# Connectors.net
KiCad netlist of a schematic drawn in Altium Designer
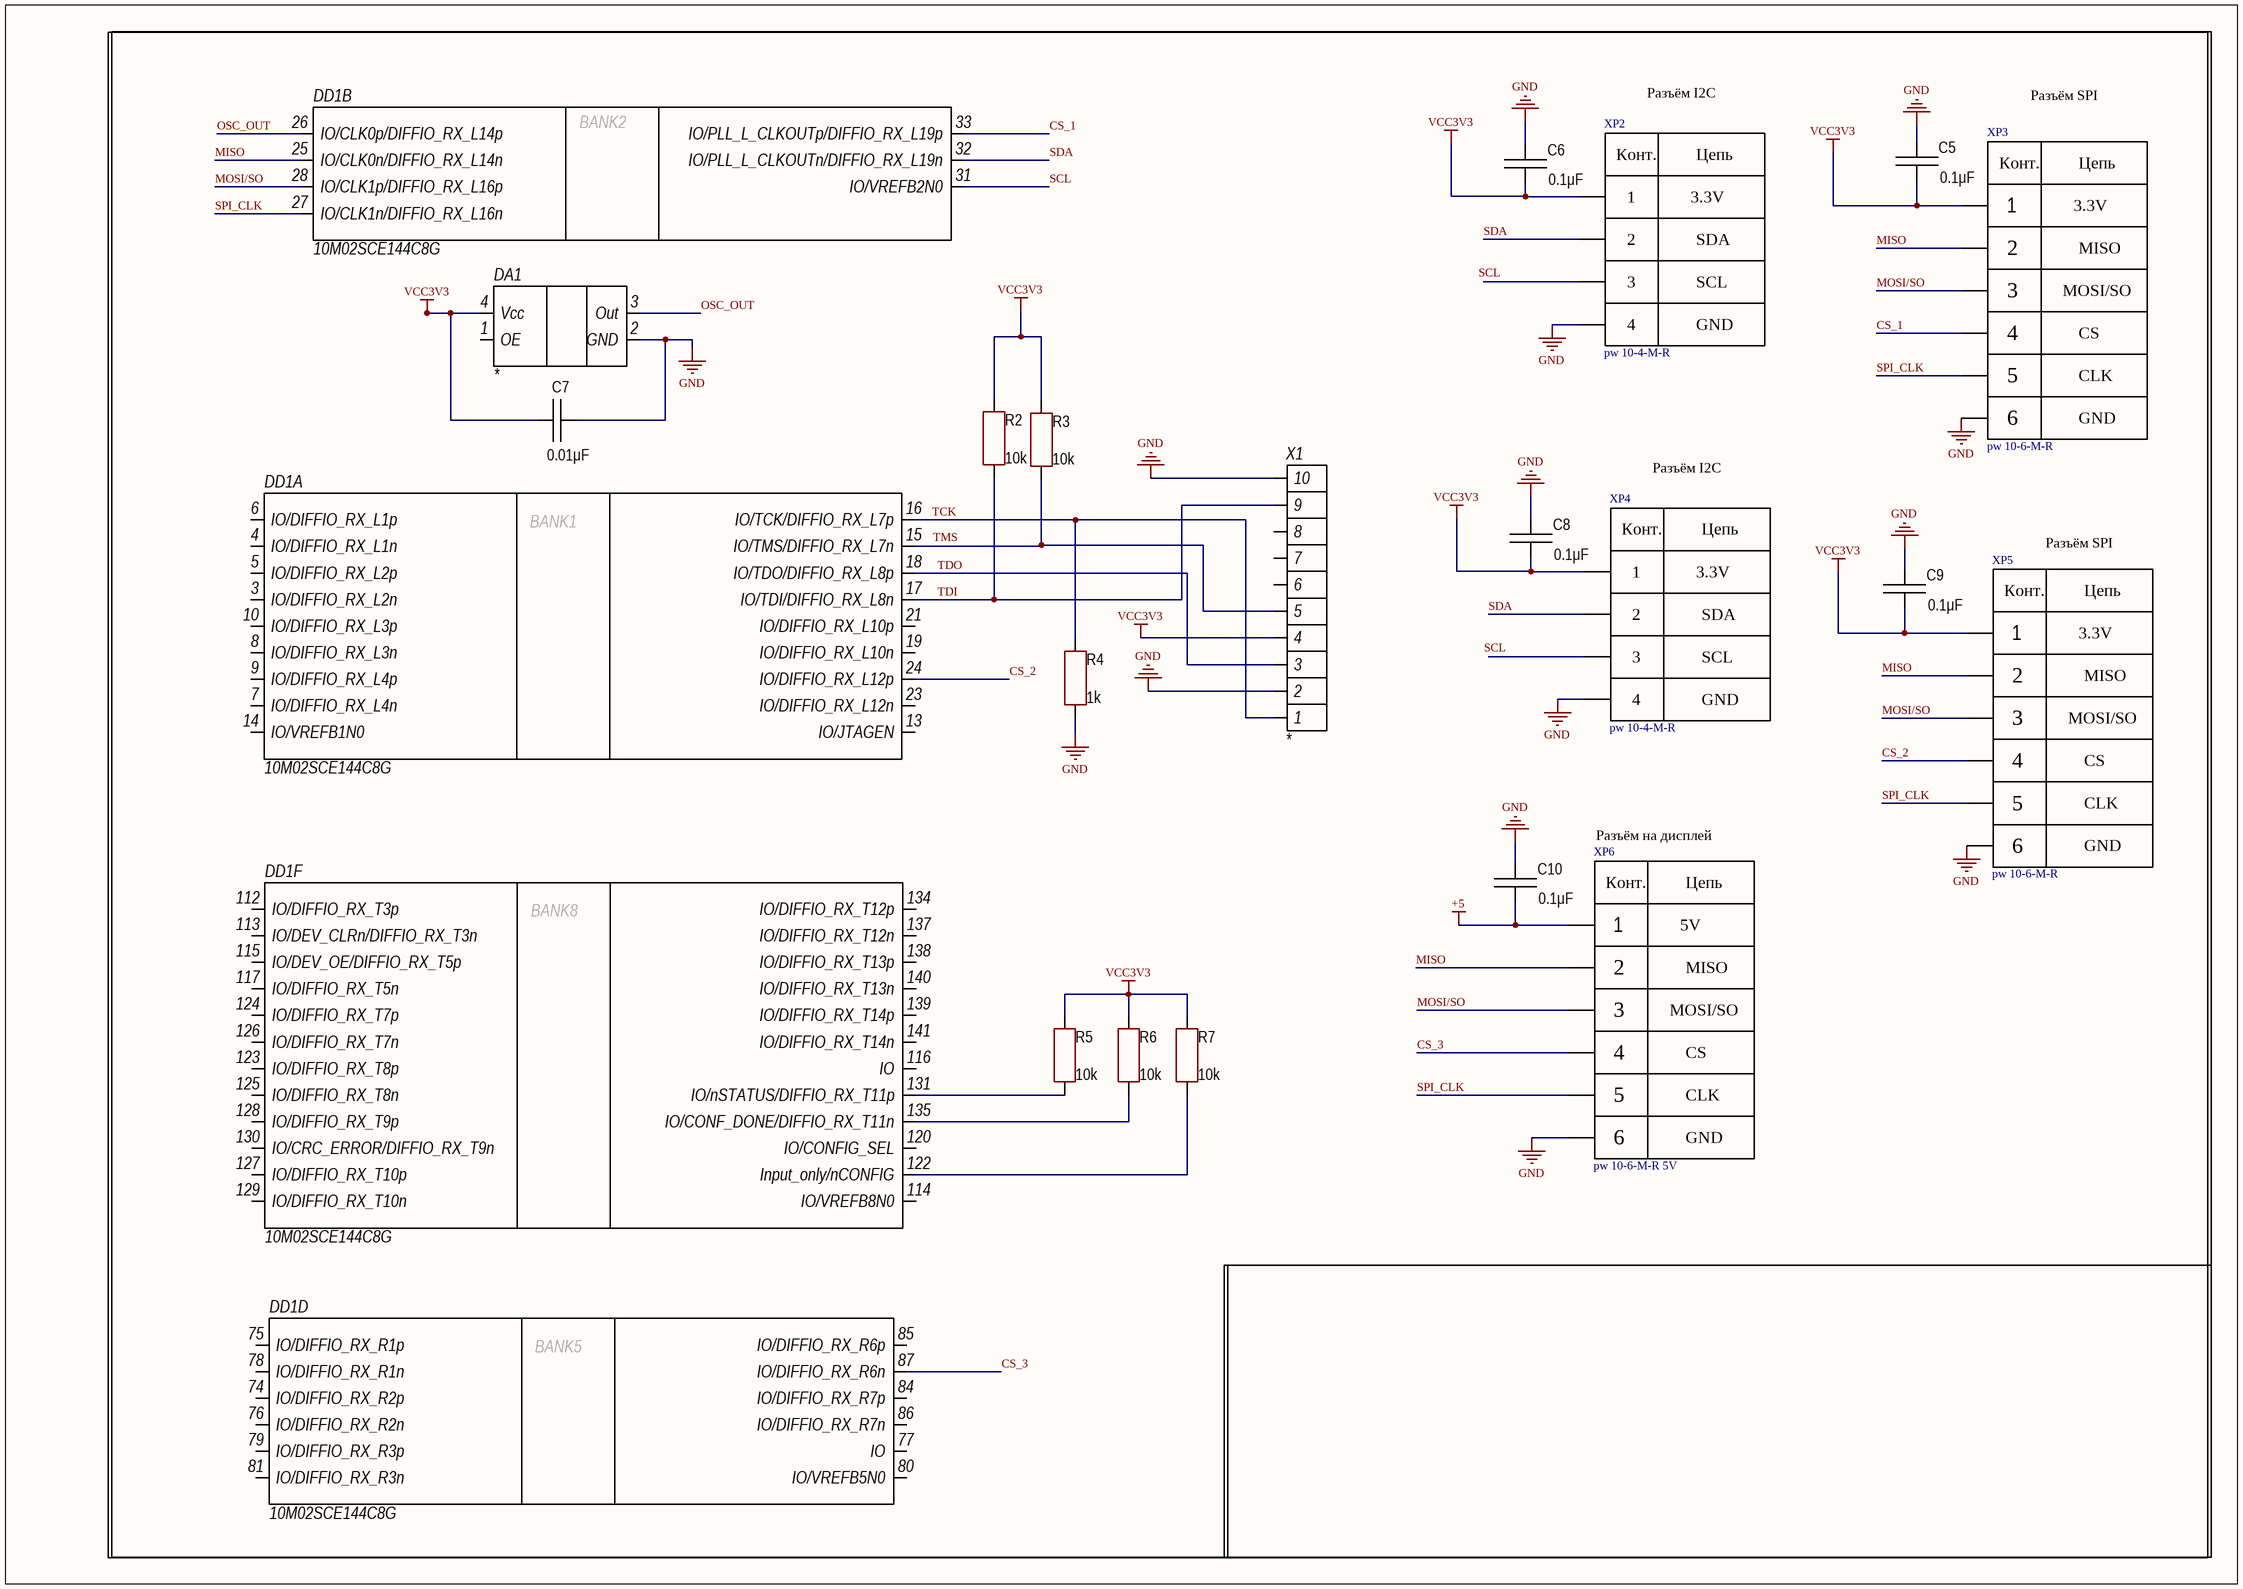
[diagram p0: Connectors.SchDoc]

(export (version "E")
  (design (tool "Eeschema 10.0.6"))
  (components
    (comp (ref "C5")
      (value "0.1μF")
      (footprint "CAP: 0805")
      (fields (field (name "VALUEMANUFACTURERPARTNUMBER") "Ceramic capacitor, 0.1μF, X7R, , , 0805, "))
      (libsource (lib "Capacitor") (part "Ceramic_0805"))
    )
    (comp (ref "C6")
      (value "0.1μF")
      (footprint "CAP: 0805")
      (fields (field (name "VALUEMANUFACTURERPARTNUMBER") "Ceramic capacitor, 0.1μF, X7R, , , 0805, "))
      (libsource (lib "Capacitor") (part "Ceramic_0805"))
    )
    (comp (ref "C7")
      (value "0.01μF")
      (footprint "CAP: 0805")
      (fields (field (name "VALUEMANUFACTURERPARTNUMBER") "Ceramic capacitor, 0.01μF, X7R, , , 0805, "))
      (libsource (lib "Capacitor") (part "Ceramic_0805"))
    )
    (comp (ref "C8")
      (value "0.1μF")
      (footprint "CAP: 0805")
      (fields (field (name "VALUEMANUFACTURERPARTNUMBER") "Ceramic capacitor, 0.1μF, X7R, , , 0805, "))
      (libsource (lib "Capacitor") (part "Ceramic_0805"))
    )
    (comp (ref "C9")
      (value "0.1μF")
      (footprint "CAP: 0805")
      (fields (field (name "VALUEMANUFACTURERPARTNUMBER") "Ceramic capacitor, 0.1μF, X7R, , , 0805, "))
      (libsource (lib "Capacitor") (part "Ceramic_0805"))
    )
    (comp (ref "C10")
      (value "0.1μF")
      (footprint "CAP: 0805")
      (fields (field (name "VALUEMANUFACTURERPARTNUMBER") "Ceramic capacitor, 0.1μF, X7R, , , 0805, "))
      (libsource (lib "Capacitor") (part "Ceramic_0805"))
    )
    (comp (ref "DA1")
      (value "*")
      (footprint "4-SMD, NO LEAD")
      (description "Oscillator")
      (fields (field (name "MANUFACTURER") "EPSON"))
      (libsource (lib "Integrated_Library") (part "SG 8002"))
    )
    (comp (ref "DD1")
      (value "10M02SCE144C8G")
      (footprint "144-Lead EQFP")
      (description "MAX10 FPGA")
      (fields (field (name "MANUFACTURER") "Intel"))
      (libsource (lib "Integrated_Library") (part "10M02SCE144C8G"))
    )
    (comp (ref "R2")
      (value "10k")
      (footprint "RES: 0805")
      (fields (field (name "VALUEMANUFACTURERPARTNUMBER") "Resistor film, 10k, , 0805, , "))
      (libsource (lib "Resistor") (part "Resistor_0805"))
    )
    (comp (ref "R3")
      (value "10k")
      (footprint "RES: 0805")
      (fields (field (name "VALUEMANUFACTURERPARTNUMBER") "Resistor film, 10k, , 0805, , "))
      (libsource (lib "Resistor") (part "Resistor_0805"))
    )
    (comp (ref "R4")
      (value "1k")
      (footprint "RES: 0805")
      (fields (field (name "VALUEMANUFACTURERPARTNUMBER") "Resistor film, 1k, , 0805, , "))
      (libsource (lib "Resistor") (part "Resistor_0805"))
    )
    (comp (ref "R5")
      (value "10k")
      (footprint "RES: 0805")
      (fields (field (name "VALUEMANUFACTURERPARTNUMBER") "Resistor film, 10k, , 0805, , "))
      (libsource (lib "Resistor") (part "Resistor_0805"))
    )
    (comp (ref "R6")
      (value "10k")
      (footprint "RES: 0805")
      (fields (field (name "VALUEMANUFACTURERPARTNUMBER") "Resistor film, 10k, , 0805, , "))
      (libsource (lib "Resistor") (part "Resistor_0805"))
    )
    (comp (ref "R7")
      (value "10k")
      (footprint "RES: 0805")
      (fields (field (name "VALUEMANUFACTURERPARTNUMBER") "Resistor film, 10k, , 0805, , "))
      (libsource (lib "Resistor") (part "Resistor_0805"))
    )
    (comp (ref "X1")
      (value "*")
      (footprint "IDC-10MS")
      (description "Connector")
      (libsource (lib "Integrated_Library") (part "Connector 10-pin"))
    )
    (comp (ref "XP2")
      (value "pw 10-4-M-R")
      (footprint "PW 10-4 - M - R")
      (libsource (lib "Integrated_Library") (part "pw 10-4-M-R"))
    )
    (comp (ref "XP3")
      (value "pw 10-6-M-R")
      (footprint "PW 10-6-M")
      (libsource (lib "Integrated_Library") (part "pw 10-6-M-R"))
    )
    (comp (ref "XP4")
      (value "pw 10-4-M-R")
      (footprint "PW 10-4 - M - R")
      (libsource (lib "Integrated_Library") (part "pw 10-4-M-R"))
    )
    (comp (ref "XP5")
      (value "pw 10-6-M-R")
      (footprint "PW 10-6-M")
      (libsource (lib "Integrated_Library") (part "pw 10-6-M-R"))
    )
    (comp (ref "XP6")
      (value "pw 10-6-M-R 5V")
      (footprint "PW 10-6-M")
      (libsource (lib "Integrated_Library") (part "pw 10-6-M-R 5V"))
    )
  )
  (nets
    (net (code "1") (name "+5") (class "Default")
      (node (ref "C10") (pin "1") (pinfunction "1_1") (pintype "power_in"))
      (node (ref "XP6") (pin "1") (pinfunction "1_1") (pintype "passive"))
    )
    (net (code "2") (name "/CS_1") (class "Default")
      (node (ref "DD1") (pin "33") (pinfunction "IO/PLL_L_CLKOUTp/DIFFIO_RX_L19p_33") (pintype "power_in"))
      (node (ref "XP3") (pin "4") (pinfunction "4_4") (pintype "passive"))
    )
    (net (code "3") (name "/CS_2") (class "Default")
      (node (ref "DD1") (pin "24") (pinfunction "IO/DIFFIO_RX_L12p_24") (pintype "power_in"))
      (node (ref "XP5") (pin "4") (pinfunction "4_4") (pintype "passive"))
    )
    (net (code "4") (name "/CS_3") (class "Default")
      (node (ref "DD1") (pin "87") (pinfunction "IO/DIFFIO_RX_R6n_87") (pintype "power_in"))
      (node (ref "XP6") (pin "4") (pinfunction "4_4") (pintype "passive"))
    )
    (net (code "5") (name "/MISO") (class "Default")
      (node (ref "DD1") (pin "25") (pinfunction "IO/CLK0n/DIFFIO_RX_L14n_25") (pintype "power_in"))
      (node (ref "XP3") (pin "2") (pinfunction "2_2") (pintype "passive"))
      (node (ref "XP5") (pin "2") (pinfunction "2_2") (pintype "passive"))
      (node (ref "XP6") (pin "2") (pinfunction "2_2") (pintype "passive"))
    )
    (net (code "6") (name "/MOSI{slash}SO") (class "Default")
      (node (ref "DD1") (pin "28") (pinfunction "IO/CLK1p/DIFFIO_RX_L16p_28") (pintype "power_in"))
      (node (ref "XP3") (pin "3") (pinfunction "3_3") (pintype "passive"))
      (node (ref "XP5") (pin "3") (pinfunction "3_3") (pintype "passive"))
      (node (ref "XP6") (pin "3") (pinfunction "3_3") (pintype "passive"))
    )
    (net (code "7") (name "/OSC_OUT") (class "Default")
      (node (ref "DA1") (pin "3") (pinfunction "Out_3") (pintype "power_in"))
      (node (ref "DD1") (pin "26") (pinfunction "IO/CLK0p/DIFFIO_RX_L14p_26") (pintype "power_in"))
    )
    (net (code "8") (name "/SCL") (class "Default")
      (node (ref "DD1") (pin "31") (pinfunction "IO/VREFB2N0_31") (pintype "power_in"))
    )
    (net (code "9") (name "/SDA") (class "Default")
      (node (ref "DD1") (pin "32") (pinfunction "IO/PLL_L_CLKOUTn/DIFFIO_RX_L19n_32") (pintype "power_in"))
      (node (ref "XP2") (pin "2") (pinfunction "2_2") (pintype "passive"))
      (node (ref "XP4") (pin "2") (pinfunction "2_2") (pintype "passive"))
    )
    (net (code "10") (name "/SPI_CLK") (class "Default")
      (node (ref "DD1") (pin "27") (pinfunction "IO/CLK1n/DIFFIO_RX_L16n_27") (pintype "power_in"))
      (node (ref "XP3") (pin "5") (pinfunction "5_5") (pintype "passive"))
      (node (ref "XP5") (pin "5") (pinfunction "5_5") (pintype "passive"))
      (node (ref "XP6") (pin "5") (pinfunction "5_5") (pintype "passive"))
    )
    (net (code "11") (name "/TCK") (class "Default")
      (node (ref "DD1") (pin "16") (pinfunction "IO/TCK/DIFFIO_RX_L7p_16") (pintype "power_in"))
      (node (ref "R4") (pin "2") (pinfunction "2_2") (pintype "passive"))
      (node (ref "X1") (pin "1") (pinfunction "1_1") (pintype "power_in"))
    )
    (net (code "12") (name "/TDI") (class "Default")
      (node (ref "DD1") (pin "17") (pinfunction "IO/TDI/DIFFIO_RX_L8n_17") (pintype "power_in"))
      (node (ref "R2") (pin "1") (pinfunction "1_1") (pintype "passive"))
      (node (ref "X1") (pin "9") (pinfunction "9_9") (pintype "power_in"))
    )
    (net (code "13") (name "/TDO") (class "Default")
      (node (ref "DD1") (pin "18") (pinfunction "IO/TDO/DIFFIO_RX_L8p_18") (pintype "power_in"))
      (node (ref "X1") (pin "3") (pinfunction "3_3") (pintype "power_in"))
    )
    (net (code "15") (name "GND") (class "Default")
      (node (ref "C10") (pin "2") (pinfunction "2_2") (pintype "power_in"))
      (node (ref "C5") (pin "2") (pinfunction "2_2") (pintype "power_in"))
      (node (ref "C6") (pin "2") (pinfunction "2_2") (pintype "power_in"))
      (node (ref "C7") (pin "1") (pinfunction "1_1") (pintype "power_in"))
      (node (ref "C8") (pin "2") (pinfunction "2_2") (pintype "power_in"))
      (node (ref "C9") (pin "2") (pinfunction "2_2") (pintype "power_in"))
      (node (ref "DA1") (pin "2") (pinfunction "GND_2") (pintype "power_in"))
      (node (ref "R4") (pin "1") (pinfunction "1_1") (pintype "passive"))
      (node (ref "X1") (pin "10") (pinfunction "10_10") (pintype "power_in"))
      (node (ref "X1") (pin "2") (pinfunction "2_2") (pintype "power_in"))
      (node (ref "XP2") (pin "4") (pinfunction "4_4") (pintype "passive"))
      (node (ref "XP3") (pin "6") (pinfunction "6_6") (pintype "passive"))
      (node (ref "XP4") (pin "4") (pinfunction "4_4") (pintype "passive"))
      (node (ref "XP5") (pin "6") (pinfunction "6_6") (pintype "passive"))
      (node (ref "XP6") (pin "6") (pinfunction "6_6") (pintype "passive"))
    )
    (net (code "16") (name "Net-(DD1A-IO{slash}TMS{slash}DIFFIO_RX_L7n)") (class "Default")
      (node (ref "DD1") (pin "15") (pinfunction "IO/TMS/DIFFIO_RX_L7n_15") (pintype "power_in"))
      (node (ref "R3") (pin "1") (pinfunction "1_1") (pintype "passive"))
      (node (ref "X1") (pin "5") (pinfunction "5_5") (pintype "power_in"))
    )
    (net (code "17") (name "Net-(DD1F-IO{slash}CONF_DONE{slash}DIFFIO_RX_T11n)") (class "Default")
      (node (ref "DD1") (pin "135") (pinfunction "IO/CONF_DONE/DIFFIO_RX_T11n_135") (pintype "power_in"))
      (node (ref "R6") (pin "1") (pinfunction "1_1") (pintype "passive"))
    )
    (net (code "18") (name "Net-(DD1F-IO{slash}nSTATUS{slash}DIFFIO_RX_T11p)") (class "Default")
      (node (ref "DD1") (pin "131") (pinfunction "IO/nSTATUS/DIFFIO_RX_T11p_131") (pintype "power_in"))
      (node (ref "R5") (pin "1") (pinfunction "1_1") (pintype "passive"))
    )
    (net (code "19") (name "Net-(DD1F-Input_only{slash}nCONFIG)") (class "Default")
      (node (ref "DD1") (pin "122") (pinfunction "Input_only/nCONFIG_122") (pintype "power_in"))
      (node (ref "R7") (pin "1") (pinfunction "1_1") (pintype "passive"))
    )
    (net (code "20") (name "VCC3V3") (class "Default")
      (node (ref "C5") (pin "1") (pinfunction "1_1") (pintype "power_in"))
      (node (ref "C6") (pin "1") (pinfunction "1_1") (pintype "power_in"))
      (node (ref "C7") (pin "2") (pinfunction "2_2") (pintype "power_in"))
      (node (ref "C8") (pin "1") (pinfunction "1_1") (pintype "power_in"))
      (node (ref "C9") (pin "1") (pinfunction "1_1") (pintype "power_in"))
      (node (ref "DA1") (pin "4") (pinfunction "Vcc_4") (pintype "power_in"))
      (node (ref "R2") (pin "2") (pinfunction "2_2") (pintype "passive"))
      (node (ref "R3") (pin "2") (pinfunction "2_2") (pintype "passive"))
      (node (ref "R5") (pin "2") (pinfunction "2_2") (pintype "passive"))
      (node (ref "R6") (pin "2") (pinfunction "2_2") (pintype "passive"))
      (node (ref "R7") (pin "2") (pinfunction "2_2") (pintype "passive"))
      (node (ref "X1") (pin "4") (pinfunction "4_4") (pintype "power_in"))
      (node (ref "XP2") (pin "1") (pinfunction "1_1") (pintype "passive"))
      (node (ref "XP3") (pin "1") (pinfunction "1_1") (pintype "passive"))
      (node (ref "XP4") (pin "1") (pinfunction "1_1") (pintype "passive"))
      (node (ref "XP5") (pin "1") (pinfunction "1_1") (pintype "passive"))
    )
    (net (code "21") (name "unconnected-(DA1-OE-Pad1)") (class "Default")
      (node (ref "DA1") (pin "1") (pinfunction "OE_1") (pintype "power_in"))
    )
    (net (code "22") (name "unconnected-(DD1A-IO{slash}DIFFIO_RX_L1n-Pad4)") (class "Default")
      (node (ref "DD1") (pin "4") (pinfunction "IO/DIFFIO_RX_L1n_4") (pintype "power_in"))
    )
    (net (code "23") (name "unconnected-(DD1A-IO{slash}DIFFIO_RX_L1p-Pad6)") (class "Default")
      (node (ref "DD1") (pin "6") (pinfunction "IO/DIFFIO_RX_L1p_6") (pintype "power_in"))
    )
    (net (code "24") (name "unconnected-(DD1A-IO{slash}DIFFIO_RX_L2n-Pad3)") (class "Default")
      (node (ref "DD1") (pin "3") (pinfunction "IO/DIFFIO_RX_L2n_3") (pintype "power_in"))
    )
    (net (code "25") (name "unconnected-(DD1A-IO{slash}DIFFIO_RX_L2p-Pad5)") (class "Default")
      (node (ref "DD1") (pin "5") (pinfunction "IO/DIFFIO_RX_L2p_5") (pintype "power_in"))
    )
    (net (code "26") (name "unconnected-(DD1A-IO{slash}DIFFIO_RX_L3n-Pad8)") (class "Default")
      (node (ref "DD1") (pin "8") (pinfunction "IO/DIFFIO_RX_L3n_8") (pintype "power_in"))
    )
    (net (code "27") (name "unconnected-(DD1A-IO{slash}DIFFIO_RX_L3p-Pad10)") (class "Default")
      (node (ref "DD1") (pin "10") (pinfunction "IO/DIFFIO_RX_L3p_10") (pintype "power_in"))
    )
    (net (code "28") (name "unconnected-(DD1A-IO{slash}DIFFIO_RX_L4n-Pad7)") (class "Default")
      (node (ref "DD1") (pin "7") (pinfunction "IO/DIFFIO_RX_L4n_7") (pintype "power_in"))
    )
    (net (code "29") (name "unconnected-(DD1A-IO{slash}DIFFIO_RX_L4p-Pad9)") (class "Default")
      (node (ref "DD1") (pin "9") (pinfunction "IO/DIFFIO_RX_L4p_9") (pintype "power_in"))
    )
    (net (code "30") (name "unconnected-(DD1A-IO{slash}DIFFIO_RX_L10n-Pad19)") (class "Default")
      (node (ref "DD1") (pin "19") (pinfunction "IO/DIFFIO_RX_L10n_19") (pintype "power_in"))
    )
    (net (code "31") (name "unconnected-(DD1A-IO{slash}DIFFIO_RX_L10p-Pad21)") (class "Default")
      (node (ref "DD1") (pin "21") (pinfunction "IO/DIFFIO_RX_L10p_21") (pintype "power_in"))
    )
    (net (code "32") (name "unconnected-(DD1A-IO{slash}DIFFIO_RX_L12n-Pad23)") (class "Default")
      (node (ref "DD1") (pin "23") (pinfunction "IO/DIFFIO_RX_L12n_23") (pintype "power_in"))
    )
    (net (code "33") (name "unconnected-(DD1A-IO{slash}JTAGEN-Pad13)") (class "Default")
      (node (ref "DD1") (pin "13") (pinfunction "IO/JTAGEN_13") (pintype "power_in"))
    )
    (net (code "34") (name "unconnected-(DD1A-IO{slash}VREFB1N0-Pad14)") (class "Default")
      (node (ref "DD1") (pin "14") (pinfunction "IO/VREFB1N0_14") (pintype "power_in"))
    )
    (net (code "35") (name "unconnected-(DD1D-IO-Pad77)") (class "Default")
      (node (ref "DD1") (pin "77") (pinfunction "IO_77") (pintype "power_in"))
    )
    (net (code "36") (name "unconnected-(DD1D-IO{slash}DIFFIO_RX_R1n-Pad78)") (class "Default")
      (node (ref "DD1") (pin "78") (pinfunction "IO/DIFFIO_RX_R1n_78") (pintype "power_in"))
    )
    (net (code "37") (name "unconnected-(DD1D-IO{slash}DIFFIO_RX_R1p-Pad75)") (class "Default")
      (node (ref "DD1") (pin "75") (pinfunction "IO/DIFFIO_RX_R1p_75") (pintype "power_in"))
    )
    (net (code "38") (name "unconnected-(DD1D-IO{slash}DIFFIO_RX_R2n-Pad76)") (class "Default")
      (node (ref "DD1") (pin "76") (pinfunction "IO/DIFFIO_RX_R2n_76") (pintype "power_in"))
    )
    (net (code "39") (name "unconnected-(DD1D-IO{slash}DIFFIO_RX_R2p-Pad74)") (class "Default")
      (node (ref "DD1") (pin "74") (pinfunction "IO/DIFFIO_RX_R2p_74") (pintype "power_in"))
    )
    (net (code "40") (name "unconnected-(DD1D-IO{slash}DIFFIO_RX_R3n-Pad81)") (class "Default")
      (node (ref "DD1") (pin "81") (pinfunction "IO/DIFFIO_RX_R3n_81") (pintype "power_in"))
    )
    (net (code "41") (name "unconnected-(DD1D-IO{slash}DIFFIO_RX_R3p-Pad79)") (class "Default")
      (node (ref "DD1") (pin "79") (pinfunction "IO/DIFFIO_RX_R3p_79") (pintype "power_in"))
    )
    (net (code "42") (name "unconnected-(DD1D-IO{slash}DIFFIO_RX_R6p-Pad85)") (class "Default")
      (node (ref "DD1") (pin "85") (pinfunction "IO/DIFFIO_RX_R6p_85") (pintype "power_in"))
    )
    (net (code "43") (name "unconnected-(DD1D-IO{slash}DIFFIO_RX_R7n-Pad86)") (class "Default")
      (node (ref "DD1") (pin "86") (pinfunction "IO/DIFFIO_RX_R7n_86") (pintype "power_in"))
    )
    (net (code "44") (name "unconnected-(DD1D-IO{slash}DIFFIO_RX_R7p-Pad84)") (class "Default")
      (node (ref "DD1") (pin "84") (pinfunction "IO/DIFFIO_RX_R7p_84") (pintype "power_in"))
    )
    (net (code "45") (name "unconnected-(DD1D-IO{slash}VREFB5N0-Pad80)") (class "Default")
      (node (ref "DD1") (pin "80") (pinfunction "IO/VREFB5N0_80") (pintype "power_in"))
    )
    (net (code "46") (name "unconnected-(DD1F-IO-Pad116)") (class "Default")
      (node (ref "DD1") (pin "116") (pinfunction "IO_116") (pintype "power_in"))
    )
    (net (code "47") (name "unconnected-(DD1F-IO{slash}CONFIG_SEL-Pad120)") (class "Default")
      (node (ref "DD1") (pin "120") (pinfunction "IO/CONFIG_SEL_120") (pintype "power_in"))
    )
    (net (code "48") (name "unconnected-(DD1F-IO{slash}CRC_ERROR{slash}DIFFIO_RX_T9n-Pad130)") (class "Default")
      (node (ref "DD1") (pin "130") (pinfunction "IO/CRC_ERROR/DIFFIO_RX_T9n_130") (pintype "power_in"))
    )
    (net (code "49") (name "unconnected-(DD1F-IO{slash}DEV_CLRn{slash}DIFFIO_RX_T3n-Pad113)") (class "Default")
      (node (ref "DD1") (pin "113") (pinfunction "IO/DEV_CLRn/DIFFIO_RX_T3n_113") (pintype "power_in"))
    )
    (net (code "50") (name "unconnected-(DD1F-IO{slash}DEV_OE{slash}DIFFIO_RX_T5p-Pad115)") (class "Default")
      (node (ref "DD1") (pin "115") (pinfunction "IO/DEV_OE/DIFFIO_RX_T5p_115") (pintype "power_in"))
    )
    (net (code "51") (name "unconnected-(DD1F-IO{slash}DIFFIO_RX_T3p-Pad112)") (class "Default")
      (node (ref "DD1") (pin "112") (pinfunction "IO/DIFFIO_RX_T3p_112") (pintype "power_in"))
    )
    (net (code "52") (name "unconnected-(DD1F-IO{slash}DIFFIO_RX_T5n-Pad117)") (class "Default")
      (node (ref "DD1") (pin "117") (pinfunction "IO/DIFFIO_RX_T5n_117") (pintype "power_in"))
    )
    (net (code "53") (name "unconnected-(DD1F-IO{slash}DIFFIO_RX_T7n-Pad126)") (class "Default")
      (node (ref "DD1") (pin "126") (pinfunction "IO/DIFFIO_RX_T7n_126") (pintype "power_in"))
    )
    (net (code "54") (name "unconnected-(DD1F-IO{slash}DIFFIO_RX_T7p-Pad124)") (class "Default")
      (node (ref "DD1") (pin "124") (pinfunction "IO/DIFFIO_RX_T7p_124") (pintype "power_in"))
    )
    (net (code "55") (name "unconnected-(DD1F-IO{slash}DIFFIO_RX_T8n-Pad125)") (class "Default")
      (node (ref "DD1") (pin "125") (pinfunction "IO/DIFFIO_RX_T8n_125") (pintype "power_in"))
    )
    (net (code "56") (name "unconnected-(DD1F-IO{slash}DIFFIO_RX_T8p-Pad123)") (class "Default")
      (node (ref "DD1") (pin "123") (pinfunction "IO/DIFFIO_RX_T8p_123") (pintype "power_in"))
    )
    (net (code "57") (name "unconnected-(DD1F-IO{slash}DIFFIO_RX_T9p-Pad128)") (class "Default")
      (node (ref "DD1") (pin "128") (pinfunction "IO/DIFFIO_RX_T9p_128") (pintype "power_in"))
    )
    (net (code "58") (name "unconnected-(DD1F-IO{slash}DIFFIO_RX_T10n-Pad129)") (class "Default")
      (node (ref "DD1") (pin "129") (pinfunction "IO/DIFFIO_RX_T10n_129") (pintype "power_in"))
    )
    (net (code "59") (name "unconnected-(DD1F-IO{slash}DIFFIO_RX_T10p-Pad127)") (class "Default")
      (node (ref "DD1") (pin "127") (pinfunction "IO/DIFFIO_RX_T10p_127") (pintype "power_in"))
    )
    (net (code "60") (name "unconnected-(DD1F-IO{slash}DIFFIO_RX_T12n-Pad137)") (class "Default")
      (node (ref "DD1") (pin "137") (pinfunction "IO/DIFFIO_RX_T12n_137") (pintype "power_in"))
    )
    (net (code "61") (name "unconnected-(DD1F-IO{slash}DIFFIO_RX_T12p-Pad134)") (class "Default")
      (node (ref "DD1") (pin "134") (pinfunction "IO/DIFFIO_RX_T12p_134") (pintype "power_in"))
    )
    (net (code "62") (name "unconnected-(DD1F-IO{slash}DIFFIO_RX_T13n-Pad140)") (class "Default")
      (node (ref "DD1") (pin "140") (pinfunction "IO/DIFFIO_RX_T13n_140") (pintype "power_in"))
    )
    (net (code "63") (name "unconnected-(DD1F-IO{slash}DIFFIO_RX_T13p-Pad138)") (class "Default")
      (node (ref "DD1") (pin "138") (pinfunction "IO/DIFFIO_RX_T13p_138") (pintype "power_in"))
    )
    (net (code "64") (name "unconnected-(DD1F-IO{slash}DIFFIO_RX_T14n-Pad141)") (class "Default")
      (node (ref "DD1") (pin "141") (pinfunction "IO/DIFFIO_RX_T14n_141") (pintype "power_in"))
    )
    (net (code "65") (name "unconnected-(DD1F-IO{slash}DIFFIO_RX_T14p-Pad139)") (class "Default")
      (node (ref "DD1") (pin "139") (pinfunction "IO/DIFFIO_RX_T14p_139") (pintype "power_in"))
    )
    (net (code "66") (name "unconnected-(DD1F-IO{slash}VREFB8N0-Pad114)") (class "Default")
      (node (ref "DD1") (pin "114") (pinfunction "IO/VREFB8N0_114") (pintype "power_in"))
    )
    (net (code "67") (name "unconnected-(X1-Pad6)") (class "Default")
      (node (ref "X1") (pin "6") (pinfunction "6_6") (pintype "power_in"))
    )
    (net (code "68") (name "unconnected-(X1-Pad7)") (class "Default")
      (node (ref "X1") (pin "7") (pinfunction "7_7") (pintype "power_in"))
    )
    (net (code "69") (name "unconnected-(X1-Pad8)") (class "Default")
      (node (ref "X1") (pin "8") (pinfunction "8_8") (pintype "power_in"))
    )
    (net (code "70") (name "unconnected-(XP2-Pad3)") (class "Default")
      (node (ref "XP2") (pin "3") (pinfunction "3_3") (pintype "passive"))
    )
    (net (code "71") (name "unconnected-(XP4-Pad3)") (class "Default")
      (node (ref "XP4") (pin "3") (pinfunction "3_3") (pintype "passive"))
    )
  )
)
